# 3_03_Power_SchDoc.net
KiCad netlist of a schematic drawn in Altium Designer
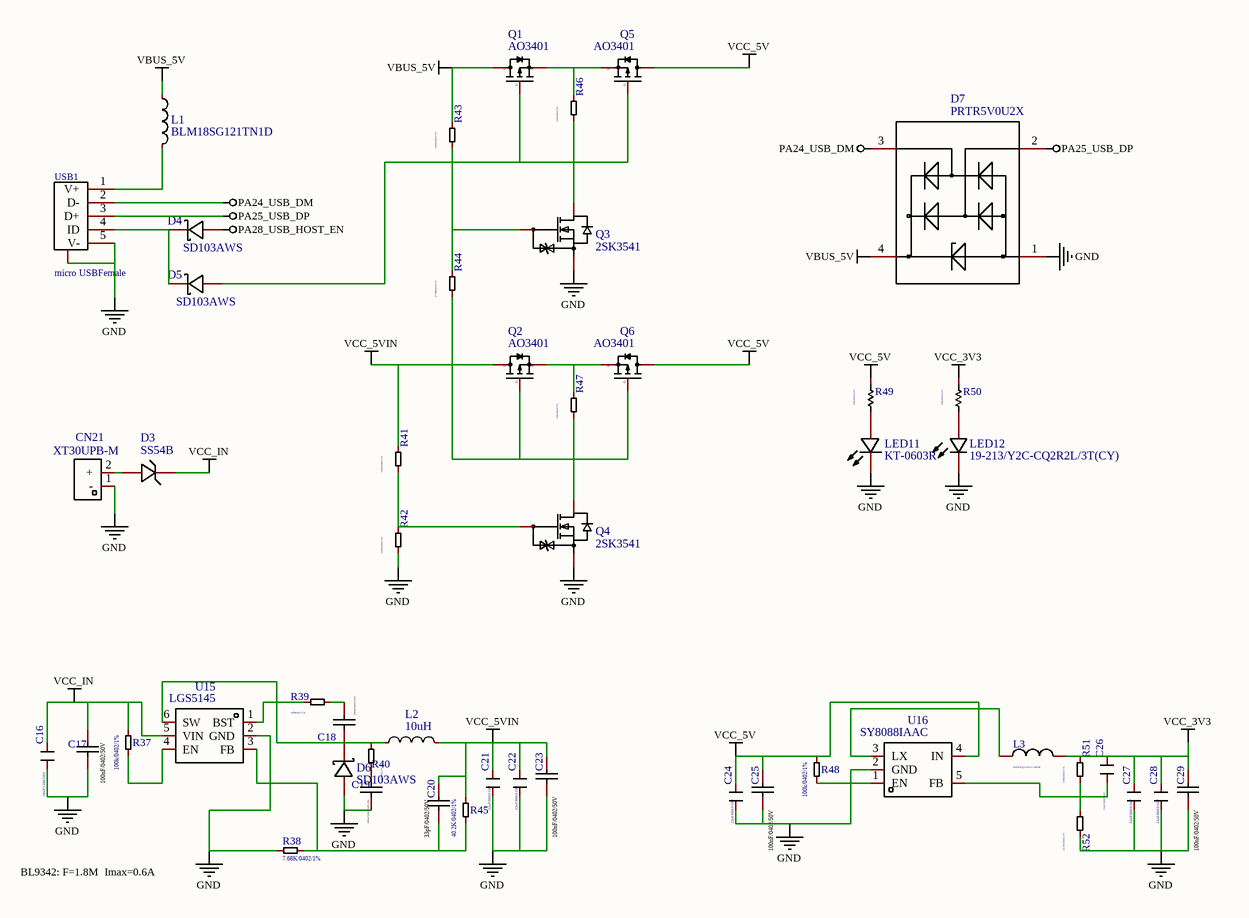
[diagram p0: 3_03 Power.SchDoc.schdoc]

(export (version "E")
  (design (tool "Eeschema 10.0.6"))
  (components
    (comp (ref "C16")
      (value "10uF/1206/50V")
      (fields (field (name "NAME") "10uF/1206/50V"))
      (libsource (lib "altium-import") (part "root_1_10uF/1206/50V_"))
    )
    (comp (ref "C17")
      (value "100nF/0603/50V")
      (fields (field (name "PUBLISHER") "Altium Limited"))
      (libsource (lib "altium-import") (part "root_1_100nF/0603/50V_"))
    )
    (comp (ref "C18")
      (value "100nF/0603/50V")
      (fields (field (name "PUBLISHER") "Altium Limited"))
      (libsource (lib "altium-import") (part "root_1_100nF/0603/50V_"))
    )
    (comp (ref "C19")
      (value "100nF/0603/50V")
      (fields (field (name "PUBLISHER") "Altium Limited"))
      (libsource (lib "altium-import") (part "root_1_100nF/0603/50V_"))
    )
    (comp (ref "C20")
      (value "100nF/0603/50V")
      (fields (field (name "PUBLISHER") "Altium Limited"))
      (libsource (lib "altium-import") (part "root_1_100nF/0603/50V_"))
    )
    (comp (ref "C21")
      (value "22uF/0603/10V")
      (fields (field (name "NAME") "22uF/0603/10V"))
      (libsource (lib "altium-import") (part "root_1_22uF/0603/10V_"))
    )
    (comp (ref "C22")
      (value "22uF/0603/10V")
      (fields (field (name "NAME") "22uF/0603/10V"))
      (libsource (lib "altium-import") (part "root_1_22uF/0603/10V_"))
    )
    (comp (ref "C23")
      (value "100nF/0603/50V")
      (fields (field (name "PUBLISHER") "Altium Limited"))
      (libsource (lib "altium-import") (part "root_1_100nF/0603/50V_"))
    )
    (comp (ref "C24")
      (value "22uF/0603/10V")
      (fields (field (name "NAME") "22uF/0603/10V"))
      (libsource (lib "altium-import") (part "root_1_22uF/0603/10V_"))
    )
    (comp (ref "C25")
      (value "100nF/0603/50V")
      (fields (field (name "PUBLISHER") "Altium Limited"))
      (libsource (lib "altium-import") (part "root_1_100nF/0603/50V_"))
    )
    (comp (ref "C26")
      (value "22pF/0402/50V")
      (fields (field (name "NAME") "22pF/0402/50V"))
      (libsource (lib "altium-import") (part "root_1_22pF/0402/50V_"))
    )
    (comp (ref "C27")
      (value "22uF/0603/10V")
      (fields (field (name "NAME") "22uF/0603/10V"))
      (libsource (lib "altium-import") (part "root_1_22uF/0603/10V_"))
    )
    (comp (ref "C28")
      (value "22uF/0603/10V")
      (fields (field (name "NAME") "22uF/0603/10V"))
      (libsource (lib "altium-import") (part "root_1_22uF/0603/10V_"))
    )
    (comp (ref "C29")
      (value "100nF/0603/50V")
      (fields (field (name "PUBLISHER") "Altium Limited"))
      (libsource (lib "altium-import") (part "root_1_100nF/0603/50V_"))
    )
    (comp (ref "CN21")
      (value "XT30UPB-M")
      (fields (field (name "NAME") "XT30UPB-M") (field (name "MANUFACTURER") "AMASS(艾迈斯)"))
      (libsource (lib "altium-import") (part "root_2_XT30UPB-M_"))
    )
    (comp (ref "D3")
      (value "SS54B")
      (fields (field (name "NAME") "SS54B") (field (name "MANUFACTURER") "PINGWEI(平伟)"))
      (libsource (lib "altium-import") (part "root_2_SS54B_"))
    )
    (comp (ref "D4")
      (value "SD103AWS")
      (fields (field (name "NAME") "SD103AWS") (field (name "MANUFACTURER") "星海"))
      (libsource (lib "altium-import") (part "root_0_SD103AWS_"))
    )
    (comp (ref "D5")
      (value "SD103AWS")
      (fields (field (name "NAME") "SD103AWS") (field (name "MANUFACTURER") "星海"))
      (libsource (lib "altium-import") (part "root_0_SD103AWS_"))
    )
    (comp (ref "D6")
      (value "SD103AWS")
      (fields (field (name "NAME") "SD103AWS") (field (name "MANUFACTURER") "星海"))
      (libsource (lib "altium-import") (part "root_3_SD103AWS_"))
    )
    (comp (ref "D7")
      (value "PRTR5V0U2X")
      (fields (field (name "NAME") "PRTR5V0U2X") (field (name "MANUFACTURER") "Yenji Elec"))
      (libsource (lib "altium-import") (part "root_2_PRTR5V0U2X_"))
    )
    (comp (ref "L1")
      (value "BLM18SG121TN1D")
      (fields (field (name "NAME") "BLM18SG121TN1D") (field (name "MANUFACTURER") "muRata(村田)"))
      (libsource (lib "altium-import") (part "root_3_BLM18SG121TN1D_"))
    )
    (comp (ref "L2")
      (value "10uH")
      (fields
        (field (name "NAME") "10uH")
        (field (name "MANUFACTURER") "Sunlord(顺络)")
        (field (name "MANUFACTURER PART") "MPL2520S100MWT")
      )
      (libsource (lib "altium-import") (part "root_0_10uH_"))
    )
    (comp (ref "L3")
      (value "PSPNAQ252012-2R2M")
      (fields (field (name "NAME") "PSPNAQ252012-2R2M"))
      (libsource (lib "altium-import") (part "root_0_PSPNAQ252012-2R2M_"))
    )
    (comp (ref "LED11")
      (value "KT-0603R")
      (fields (field (name "NAME") "KT-0603R") (field (name "MANUFACTURER") "KENTO"))
      (libsource (lib "altium-import") (part "root_1_KT-0603R_"))
    )
    (comp (ref "LED12")
      (value "19-213/Y2C-CQ2R2L/3T(CY)")
      (fields (field (name "NAME") "19-213/Y2C-CQ2R2L/3T(CY)") (field (name "MANUFACTURER") "EVERLIGHT(亿光)"))
      (libsource (lib "altium-import") (part "root_1_19-213/Y2C-CQ2R2L/3T(CY)_"))
    )
    (comp (ref "Q1")
      (value "AO3401")
      (fields (field (name "NAME") "AO3401") (field (name "MANUFACTURER") "Hottech(合科泰)"))
      (libsource (lib "") (part "root_1_AO3401__1"))
    )
    (comp (ref "Q2")
      (value "AO3401")
      (fields (field (name "NAME") "AO3401") (field (name "MANUFACTURER") "Hottech(合科泰)"))
      (libsource (lib "") (part "root_1_AO3401__1"))
    )
    (comp (ref "Q3")
      (value "2SK3541")
      (fields (field (name "NAME") "2SK3541") (field (name "MANUFACTURER") "CJ（江苏长电/长晶）"))
      (libsource (lib "altium-import") (part "root_0_2SK3541_"))
    )
    (comp (ref "Q4")
      (value "2SK3541")
      (fields (field (name "NAME") "2SK3541") (field (name "MANUFACTURER") "CJ（江苏长电/长晶）"))
      (libsource (lib "altium-import") (part "root_0_2SK3541_"))
    )
    (comp (ref "Q5")
      (value "AO3401")
      (fields (field (name "NAME") "AO3401") (field (name "MANUFACTURER") "Hottech(合科泰)"))
      (libsource (lib "altium-import") (part "root_1_AO3401_"))
    )
    (comp (ref "Q6")
      (value "AO3401")
      (fields (field (name "NAME") "AO3401") (field (name "MANUFACTURER") "Hottech(合科泰)"))
      (libsource (lib "altium-import") (part "root_1_AO3401_"))
    )
    (comp (ref "R37")
      (value "100k/0402/1%")
      (fields (field (name "NAME") "100k/0402/1%"))
      (libsource (lib "altium-import") (part "root_1_100k/0402/1%_"))
    )
    (comp (ref "R38")
      (value "7.68K/0402/1%")
      (fields (field (name "NAME") "7.68K/0402/1%"))
      (libsource (lib "altium-import") (part "root_2_7.68K/0402/1%_"))
    )
    (comp (ref "R39")
      (value "10R/0402/1%")
      (fields (field (name "NAME") "10R/0402/1%"))
      (libsource (lib "altium-import") (part "root_0_10R/0402/1%_"))
    )
    (comp (ref "R40")
      (value "10R/0402/1%-NC")
      (fields (field (name "NAME") "10R/0402/1%-NC"))
      (libsource (lib "altium-import") (part "root_1_10R/0402/1%-NC_"))
    )
    (comp (ref "R41")
      (value "100k/0402/1%")
      (fields (field (name "NAME") "100k/0402/1%"))
      (libsource (lib "altium-import") (part "root_1_100k/0402/1%_"))
    )
    (comp (ref "R42")
      (value "100k/0402/1%")
      (fields (field (name "NAME") "100k/0402/1%"))
      (libsource (lib "altium-import") (part "root_1_100k/0402/1%_"))
    )
    (comp (ref "R43")
      (value "100k/0402/1%")
      (fields (field (name "NAME") "100k/0402/1%"))
      (libsource (lib "altium-import") (part "root_1_100k/0402/1%_"))
    )
    (comp (ref "R44")
      (value "470R/0402/1%")
      (fields (field (name "NAME") "470R/0402/1%"))
      (libsource (lib "altium-import") (part "root_1_470R/0402/1%_"))
    )
    (comp (ref "R45")
      (value "40.2K/0402/1%")
      (fields (field (name "NAME") "40.2K/0402/1%"))
      (libsource (lib "altium-import") (part "root_1_40.2K/0402/1%_"))
    )
    (comp (ref "R46")
      (value "10k/0402/1%")
      (fields (field (name "NAME") "10k/0402/1%"))
      (libsource (lib "altium-import") (part "root_1_10k/0402/1%_"))
    )
    (comp (ref "R47")
      (value "10k/0402/1%")
      (fields (field (name "NAME") "10k/0402/1%"))
      (libsource (lib "altium-import") (part "root_1_10k/0402/1%_"))
    )
    (comp (ref "R48")
      (value "100k/0402/1%")
      (fields (field (name "NAME") "100k/0402/1%"))
      (libsource (lib "altium-import") (part "root_1_100k/0402/1%_"))
    )
    (comp (ref "R49")
      (value "10K/0402/1%")
      (fields (field (name "NAME") "10K/0402/1%") (field (name "PUBLISHER") "Altium Limited"))
      (libsource (lib "altium-import") (part "root_1_10K/0402/1%_"))
    )
    (comp (ref "R50")
      (value "10K/0402/1%")
      (fields (field (name "NAME") "10K/0402/1%") (field (name "PUBLISHER") "Altium Limited"))
      (libsource (lib "altium-import") (part "root_1_10K/0402/1%_"))
    )
    (comp (ref "R51")
      (value "100k/0402/1%")
      (fields (field (name "NAME") "100k/0402/1%"))
      (libsource (lib "altium-import") (part "root_1_100k/0402/1%_"))
    )
    (comp (ref "R52")
      (value "22.1K/0402/1%")
      (fields (field (name "NAME") "22.1K/0402/1%"))
      (libsource (lib "altium-import") (part "root_1_22.1K/0402/1%_"))
    )
    (comp (ref "U15")
      (value "LGS5145")
      (fields (field (name "NAME") "LGS5145") (field (name "MANUFACTURER") "Legend-Si(棱晶半导体)"))
      (libsource (lib "altium-import") (part "root_0_LGS5145_"))
    )
    (comp (ref "U16")
      (value "SY8088IAAC")
      (fields (field (name "NAME") "SY8088IAAC") (field (name "MANUFACTURER") "silergy(矽力杰)"))
      (libsource (lib "altium-import") (part "root_2_SY8088IAAC_"))
    )
    (comp (ref "USB1")
      (value "micro USBFemale")
      (fields (field (name "NAME") "micro USBFemale") (field (name "MANUFACTURER") "ValuePro"))
      (libsource (lib "altium-import") (part "root_0_micro USBFemale_"))
    )
  )
  (nets
    (net (code "1") (name "GND") (class "Default")
      (node (ref "C16") (pin "1") (pinfunction "1_1") (pintype "passive"))
      (node (ref "C17") (pin "1") (pinfunction "1_1") (pintype "passive"))
      (node (ref "C19") (pin "1") (pinfunction "1_1") (pintype "passive"))
      (node (ref "C21") (pin "1") (pinfunction "1_1") (pintype "passive"))
      (node (ref "C22") (pin "1") (pinfunction "1_1") (pintype "passive"))
      (node (ref "C23") (pin "1") (pinfunction "1_1") (pintype "passive"))
      (node (ref "C24") (pin "1") (pinfunction "1_1") (pintype "passive"))
      (node (ref "C25") (pin "1") (pinfunction "1_1") (pintype "passive"))
      (node (ref "C27") (pin "1") (pinfunction "1_1") (pintype "passive"))
      (node (ref "C28") (pin "1") (pinfunction "1_1") (pintype "passive"))
      (node (ref "C29") (pin "1") (pinfunction "1_1") (pintype "passive"))
      (node (ref "CN21") (pin "1") (pinfunction "-_1") (pintype "passive"))
      (node (ref "D6") (pin "2") (pinfunction "A_2") (pintype "passive"))
      (node (ref "D7") (pin "1") (pinfunction "GND_1") (pintype "passive"))
      (node (ref "LED11") (pin "1") (pinfunction "K_1") (pintype "passive"))
      (node (ref "LED12") (pin "1") (pinfunction "C_1") (pintype "passive"))
      (node (ref "Q3") (pin "2") (pinfunction "S_2") (pintype "passive"))
      (node (ref "Q4") (pin "2") (pinfunction "S_2") (pintype "passive"))
      (node (ref "R38") (pin "2") (pinfunction "2_2") (pintype "passive"))
      (node (ref "R42") (pin "1") (pinfunction "1_1") (pintype "passive"))
      (node (ref "R52") (pin "1") (pinfunction "1_1") (pintype "passive"))
      (node (ref "U15") (pin "2") (pinfunction "GND_2") (pintype "passive"))
      (node (ref "U16") (pin "2") (pinfunction "GND_2") (pintype "passive"))
      (node (ref "USB1") (pin "5") (pinfunction "V-_5") (pintype "passive"))
    )
    (net (code "2") (name "Net-(C18-Pad2)") (class "Default")
      (node (ref "C18") (pin "2") (pinfunction "2_2") (pintype "passive"))
      (node (ref "R39") (pin "2") (pinfunction "2_2") (pintype "passive"))
    )
    (net (code "3") (name "Net-(C19-Pad2)") (class "Default")
      (node (ref "C19") (pin "2") (pinfunction "2_2") (pintype "passive"))
      (node (ref "R40") (pin "1") (pinfunction "1_1") (pintype "passive"))
    )
    (net (code "4") (name "Net-(CN21-+)") (class "Default")
      (node (ref "CN21") (pin "2") (pinfunction "+_2") (pintype "passive"))
      (node (ref "D3") (pin "2") (pinfunction "A_2") (pintype "passive"))
    )
    (net (code "5") (name "Net-(D4-K)") (class "Default")
      (node (ref "D4") (pin "1") (pinfunction "K_1") (pintype "passive"))
      (node (ref "D5") (pin "1") (pinfunction "K_1") (pintype "passive"))
      (node (ref "USB1") (pin "4") (pinfunction "ID_4") (pintype "passive"))
    )
    (net (code "6") (name "Net-(D5-A)") (class "Default")
      (node (ref "D5") (pin "2") (pinfunction "A_2") (pintype "passive"))
      (node (ref "Q1") (pin "1") (pinfunction "G_1") (pintype "passive"))
      (node (ref "Q3") (pin "3") (pinfunction "D_3") (pintype "passive"))
      (node (ref "Q5") (pin "1") (pinfunction "G_1") (pintype "passive"))
      (node (ref "R46") (pin "1") (pinfunction "1_1") (pintype "passive"))
    )
    (net (code "7") (name "Net-(D6-K)") (class "Default")
      (node (ref "C18") (pin "1") (pinfunction "1_1") (pintype "passive"))
      (node (ref "D6") (pin "1") (pinfunction "K_1") (pintype "passive"))
      (node (ref "L2") (pin "1") (pinfunction "1_1") (pintype "passive"))
      (node (ref "R40") (pin "2") (pinfunction "2_2") (pintype "passive"))
      (node (ref "U15") (pin "6") (pinfunction "SW_6") (pintype "passive"))
    )
    (net (code "8") (name "Net-(LED11-A)") (class "Default")
      (node (ref "LED11") (pin "2") (pinfunction "A_2") (pintype "passive"))
      (node (ref "R49") (pin "1") (pinfunction "1_1") (pintype "passive"))
    )
    (net (code "9") (name "Net-(LED12-A)") (class "Default")
      (node (ref "LED12") (pin "2") (pinfunction "A_2") (pintype "passive"))
      (node (ref "R50") (pin "1") (pinfunction "1_1") (pintype "passive"))
    )
    (net (code "10") (name "Net-(Q1-S)") (class "Default")
      (node (ref "Q1") (pin "2") (pinfunction "S_2") (pintype "passive"))
      (node (ref "Q5") (pin "2") (pinfunction "S_2") (pintype "passive"))
      (node (ref "R46") (pin "2") (pinfunction "2_2") (pintype "passive"))
    )
    (net (code "11") (name "Net-(Q2-G)") (class "Default")
      (node (ref "Q2") (pin "1") (pinfunction "G_1") (pintype "passive"))
      (node (ref "Q4") (pin "3") (pinfunction "D_3") (pintype "passive"))
      (node (ref "Q6") (pin "1") (pinfunction "G_1") (pintype "passive"))
      (node (ref "R44") (pin "1") (pinfunction "1_1") (pintype "passive"))
      (node (ref "R47") (pin "1") (pinfunction "1_1") (pintype "passive"))
    )
    (net (code "12") (name "Net-(Q2-S)") (class "Default")
      (node (ref "Q2") (pin "2") (pinfunction "S_2") (pintype "passive"))
      (node (ref "Q6") (pin "2") (pinfunction "S_2") (pintype "passive"))
      (node (ref "R47") (pin "2") (pinfunction "2_2") (pintype "passive"))
    )
    (net (code "13") (name "Net-(Q3-G)") (class "Default")
      (node (ref "Q3") (pin "1") (pinfunction "G_1") (pintype "passive"))
      (node (ref "R43") (pin "1") (pinfunction "1_1") (pintype "passive"))
      (node (ref "R44") (pin "2") (pinfunction "2_2") (pintype "passive"))
    )
    (net (code "14") (name "Net-(Q4-G)") (class "Default")
      (node (ref "Q4") (pin "1") (pinfunction "G_1") (pintype "passive"))
      (node (ref "R41") (pin "1") (pinfunction "1_1") (pintype "passive"))
      (node (ref "R42") (pin "2") (pinfunction "2_2") (pintype "passive"))
    )
    (net (code "15") (name "Net-(U15-BST)") (class "Default")
      (node (ref "R39") (pin "1") (pinfunction "1_1") (pintype "passive"))
      (node (ref "U15") (pin "1") (pinfunction "BST_1") (pintype "passive"))
    )
    (net (code "16") (name "Net-(U15-EN)") (class "Default")
      (node (ref "R37") (pin "1") (pinfunction "1_1") (pintype "passive"))
      (node (ref "U15") (pin "4") (pinfunction "EN_4") (pintype "passive"))
    )
    (net (code "17") (name "Net-(U15-FB)") (class "Default")
      (node (ref "C20") (pin "1") (pinfunction "1_1") (pintype "passive"))
      (node (ref "R38") (pin "1") (pinfunction "1_1") (pintype "passive"))
      (node (ref "R45") (pin "1") (pinfunction "1_1") (pintype "passive"))
      (node (ref "U15") (pin "3") (pinfunction "FB_3") (pintype "passive"))
    )
    (net (code "18") (name "Net-(U16-EN)") (class "Default")
      (node (ref "R48") (pin "1") (pinfunction "1_1") (pintype "passive"))
      (node (ref "U16") (pin "1") (pinfunction "EN_1") (pintype "passive"))
    )
    (net (code "19") (name "Net-(U16-FB)") (class "Default")
      (node (ref "C26") (pin "1") (pinfunction "1_1") (pintype "passive"))
      (node (ref "R51") (pin "1") (pinfunction "1_1") (pintype "passive"))
      (node (ref "R52") (pin "2") (pinfunction "2_2") (pintype "passive"))
      (node (ref "U16") (pin "5") (pinfunction "FB_5") (pintype "passive"))
    )
    (net (code "20") (name "Net-(U16-LX)") (class "Default")
      (node (ref "L3") (pin "1") (pinfunction "1_1") (pintype "passive"))
      (node (ref "U16") (pin "3") (pinfunction "LX_3") (pintype "passive"))
    )
    (net (code "21") (name "Net-(USB1-V+)") (class "Default")
      (node (ref "L1") (pin "2") (pinfunction "2_2") (pintype "passive"))
      (node (ref "USB1") (pin "1") (pinfunction "V+_1") (pintype "passive"))
    )
    (net (code "22") (name "PA24_USB_DM") (class "Default")
      (node (ref "D7") (pin "3") (pinfunction "IO2_3") (pintype "passive"))
      (node (ref "USB1") (pin "2") (pinfunction "D-_2") (pintype "passive"))
    )
    (net (code "23") (name "PA25_USB_DP") (class "Default")
      (node (ref "D7") (pin "2") (pinfunction "IO1_2") (pintype "passive"))
      (node (ref "USB1") (pin "3") (pinfunction "D+_3") (pintype "passive"))
    )
    (net (code "24") (name "PA28_USB_HOST_EN") (class "Default")
      (node (ref "D4") (pin "2") (pinfunction "A_2") (pintype "passive"))
    )
    (net (code "25") (name "VBUS_5V") (class "Default")
      (node (ref "D7") (pin "4") (pinfunction "VCC_4") (pintype "passive"))
      (node (ref "L1") (pin "1") (pinfunction "1_1") (pintype "passive"))
      (node (ref "Q1") (pin "3") (pinfunction "D_3") (pintype "passive"))
      (node (ref "R43") (pin "2") (pinfunction "2_2") (pintype "passive"))
    )
    (net (code "26") (name "VCC_3V3") (class "Default")
      (node (ref "C26") (pin "2") (pinfunction "2_2") (pintype "passive"))
      (node (ref "C27") (pin "2") (pinfunction "2_2") (pintype "passive"))
      (node (ref "C28") (pin "2") (pinfunction "2_2") (pintype "passive"))
      (node (ref "C29") (pin "2") (pinfunction "2_2") (pintype "passive"))
      (node (ref "L3") (pin "2") (pinfunction "2_2") (pintype "passive"))
      (node (ref "R50") (pin "2") (pinfunction "2_2") (pintype "passive"))
      (node (ref "R51") (pin "2") (pinfunction "2_2") (pintype "passive"))
    )
    (net (code "27") (name "VCC_5V") (class "Default")
      (node (ref "C24") (pin "2") (pinfunction "2_2") (pintype "passive"))
      (node (ref "C25") (pin "2") (pinfunction "2_2") (pintype "passive"))
      (node (ref "Q5") (pin "3") (pinfunction "D_3") (pintype "passive"))
      (node (ref "Q6") (pin "3") (pinfunction "D_3") (pintype "passive"))
      (node (ref "R48") (pin "2") (pinfunction "2_2") (pintype "passive"))
      (node (ref "R49") (pin "2") (pinfunction "2_2") (pintype "passive"))
      (node (ref "U16") (pin "4") (pinfunction "IN_4") (pintype "passive"))
    )
    (net (code "28") (name "VCC_5VIN") (class "Default")
      (node (ref "C20") (pin "2") (pinfunction "2_2") (pintype "passive"))
      (node (ref "C21") (pin "2") (pinfunction "2_2") (pintype "passive"))
      (node (ref "C22") (pin "2") (pinfunction "2_2") (pintype "passive"))
      (node (ref "C23") (pin "2") (pinfunction "2_2") (pintype "passive"))
      (node (ref "L2") (pin "2") (pinfunction "2_2") (pintype "passive"))
      (node (ref "Q2") (pin "3") (pinfunction "D_3") (pintype "passive"))
      (node (ref "R41") (pin "2") (pinfunction "2_2") (pintype "passive"))
      (node (ref "R45") (pin "2") (pinfunction "2_2") (pintype "passive"))
    )
    (net (code "29") (name "VCC_IN") (class "Default")
      (node (ref "C16") (pin "2") (pinfunction "2_2") (pintype "passive"))
      (node (ref "C17") (pin "2") (pinfunction "2_2") (pintype "passive"))
      (node (ref "D3") (pin "1") (pinfunction "C_1") (pintype "passive"))
      (node (ref "R37") (pin "2") (pinfunction "2_2") (pintype "passive"))
      (node (ref "U15") (pin "5") (pinfunction "VIN_5") (pintype "passive"))
    )
  )
)
